# PowerNode2.net
KiCad netlist of a schematic drawn in EAGLE
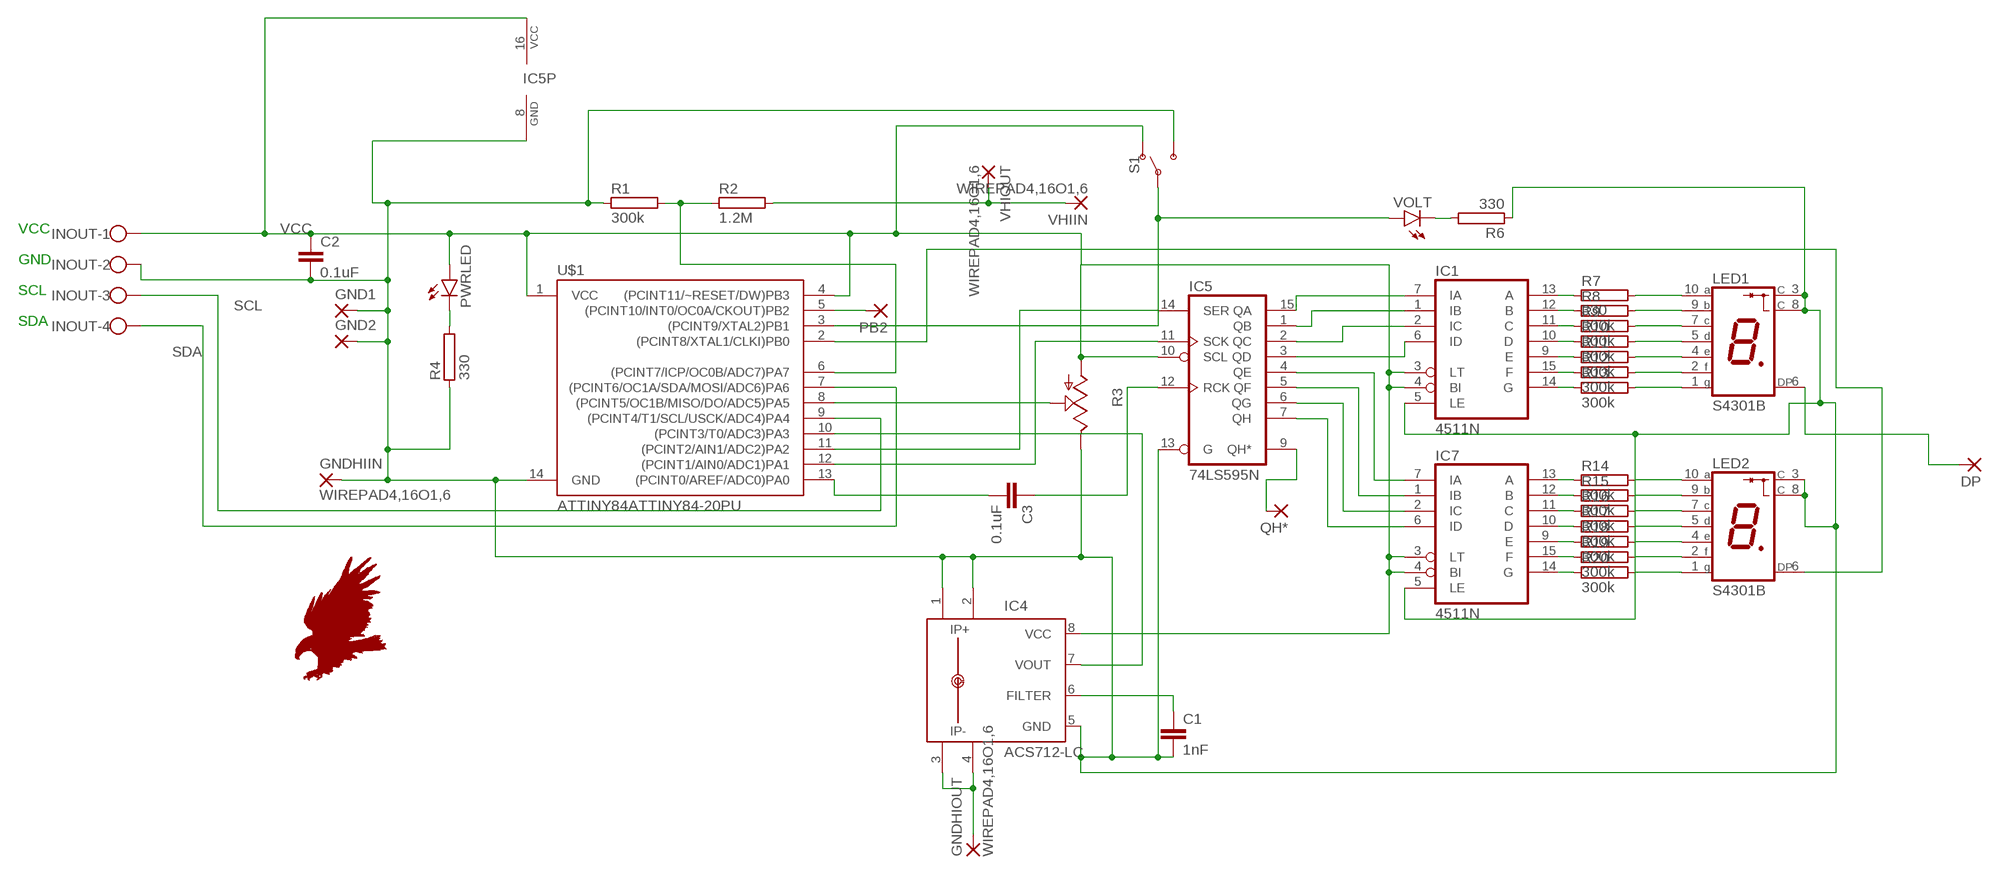
[diagram p0: schematic, sheet 1]

(export (version "E")
  (design (tool "Eeschema 10.0.6"))
  (components
    (comp (ref "C1")
      (value "1nF")
      (footprint "eagle-import:C5B3")
      (libsource (lib "eagle-import") (part "C5/3"))
    )
    (comp (ref "C2")
      (value "0.1uF")
      (footprint "eagle-import:C5B3")
      (libsource (lib "eagle-import") (part "C5/3"))
    )
    (comp (ref "C3")
      (value "0.1uF")
      (footprint "eagle-import:C5B3")
      (libsource (lib "eagle-import") (part "C5/3"))
    )
    (comp (ref "DP")
      (value "2,54/0,9")
      (footprint "eagle-import:2,54_0,9")
      (libsource (lib "eagle-import") (part "2,54/0,9"))
    )
    (comp (ref "GND1")
      (value "2,15/1,0")
      (footprint "eagle-import:2,15_1,0")
      (libsource (lib "eagle-import") (part "2,15/1,0"))
    )
    (comp (ref "GND2")
      (value "2,15/1,0")
      (footprint "eagle-import:2,15_1,0")
      (libsource (lib "eagle-import") (part "2,15/1,0"))
    )
    (comp (ref "GNDHIIN")
      (value "WIREPAD4,16O1,6")
      (footprint "eagle-import:4,16O1,6")
      (libsource (lib "eagle-import") (part "WIREPAD4,16O1,6"))
    )
    (comp (ref "GNDHIOUT")
      (value "WIREPAD4,16O1,6")
      (footprint "eagle-import:4,16O1,6")
      (libsource (lib "eagle-import") (part "WIREPAD4,16O1,6"))
    )
    (comp (ref "IC1")
      (value "4511N")
      (footprint "eagle-import:DIL16")
      (libsource (lib "eagle-import") (part "4511N"))
    )
    (comp (ref "IC4")
      (value "ACS712-LC")
      (footprint "eagle-import:SOIC8")
      (libsource (lib "eagle-import") (part "ACS712-LC"))
    )
    (comp (ref "IC5")
      (value "74LS595N")
      (footprint "eagle-import:DIL16")
      (libsource (lib "eagle-import") (part "74595NLS"))
    )
    (comp (ref "IC7")
      (value "4511N")
      (footprint "eagle-import:DIL16")
      (libsource (lib "eagle-import") (part "4511N"))
    )
    (comp (ref "INOUT")
      (value "W237-4")
      (footprint "eagle-import:W237-4")
      (libsource (lib "eagle-import") (part "W237-4"))
    )
    (comp (ref "LED1")
      (value "S4301B")
      (footprint "eagle-import:S4301B")
      (libsource (lib "eagle-import") (part "S4301B"))
    )
    (comp (ref "LED2")
      (value "S4301B")
      (footprint "eagle-import:S4301B")
      (libsource (lib "eagle-import") (part "S4301B"))
    )
    (comp (ref "PB2")
      (value "2,54/0,9")
      (footprint "eagle-import:2,54_0,9")
      (libsource (lib "eagle-import") (part "2,54/0,9"))
    )
    (comp (ref "PWRLED")
      (value "LED5MM")
      (footprint "eagle-import:LED5MM")
      (libsource (lib "eagle-import") (part "LED5MM"))
    )
    (comp (ref "QH*")
      (value "2,54/0,9")
      (footprint "eagle-import:2,54_0,9")
      (libsource (lib "eagle-import") (part "2,54/0,9"))
    )
    (comp (ref "R1")
      (value "300k")
      (footprint "eagle-import:KH206-8R")
      (libsource (lib "eagle-import") (part "RKH206-8R"))
    )
    (comp (ref "R2")
      (value "1.2M")
      (footprint "eagle-import:KH206-8R")
      (libsource (lib "eagle-import") (part "RKH206-8R"))
    )
    (comp (ref "R3")
      (value "TRIM_US-B25P")
      (footprint "eagle-import:B25P")
      (libsource (lib "eagle-import") (part "TRIM_US-B25P"))
    )
    (comp (ref "R4")
      (value "330")
      (footprint "eagle-import:KH206-8R")
      (libsource (lib "eagle-import") (part "RKH206-8R"))
    )
    (comp (ref "R6")
      (value "330")
      (footprint "eagle-import:KH206-8R")
      (libsource (lib "eagle-import") (part "RKH206-8R"))
    )
    (comp (ref "R7")
      (value "330")
      (footprint "eagle-import:KH206-8R")
      (libsource (lib "eagle-import") (part "RKH206-8R"))
    )
    (comp (ref "R8")
      (value "300k")
      (footprint "eagle-import:KH206-8R")
      (libsource (lib "eagle-import") (part "RKH206-8R"))
    )
    (comp (ref "R9")
      (value "300k")
      (footprint "eagle-import:KH206-8R")
      (libsource (lib "eagle-import") (part "RKH206-8R"))
    )
    (comp (ref "R10")
      (value "300k")
      (footprint "eagle-import:KH206-8R")
      (libsource (lib "eagle-import") (part "RKH206-8R"))
    )
    (comp (ref "R11")
      (value "300k")
      (footprint "eagle-import:KH206-8R")
      (libsource (lib "eagle-import") (part "RKH206-8R"))
    )
    (comp (ref "R12")
      (value "300k")
      (footprint "eagle-import:KH206-8R")
      (libsource (lib "eagle-import") (part "RKH206-8R"))
    )
    (comp (ref "R13")
      (value "300k")
      (footprint "eagle-import:KH206-8R")
      (libsource (lib "eagle-import") (part "RKH206-8R"))
    )
    (comp (ref "R14")
      (value "300k")
      (footprint "eagle-import:KH206-8R")
      (libsource (lib "eagle-import") (part "RKH206-8R"))
    )
    (comp (ref "R15")
      (value "300k")
      (footprint "eagle-import:KH206-8R")
      (libsource (lib "eagle-import") (part "RKH206-8R"))
    )
    (comp (ref "R16")
      (value "300k")
      (footprint "eagle-import:KH206-8R")
      (libsource (lib "eagle-import") (part "RKH206-8R"))
    )
    (comp (ref "R17")
      (value "300k")
      (footprint "eagle-import:KH206-8R")
      (libsource (lib "eagle-import") (part "RKH206-8R"))
    )
    (comp (ref "R18")
      (value "300k")
      (footprint "eagle-import:KH206-8R")
      (libsource (lib "eagle-import") (part "RKH206-8R"))
    )
    (comp (ref "R19")
      (value "300k")
      (footprint "eagle-import:KH206-8R")
      (libsource (lib "eagle-import") (part "RKH206-8R"))
    )
    (comp (ref "R20")
      (value "300k")
      (footprint "eagle-import:KH206-8R")
      (libsource (lib "eagle-import") (part "RKH206-8R"))
    )
    (comp (ref "S1")
      (value "SWITCH-SPDT-PTH-11.6X4.0MM")
      (footprint "eagle-import:SWITCH_SPDT_PTH_11.6X4.0MM")
      (libsource (lib "eagle-import") (part "SWITCH-SPDT-PTH-11.6X4.0MM"))
    )
    (comp (ref "U$1")
      (value "ATTINY84ATTINY84-20PU")
      (footprint "eagle-import:DIP14")
      (libsource (lib "eagle-import") (part "ATTINY84ATTINY84-20PU"))
    )
    (comp (ref "VHIIN")
      (value "WIREPAD4,16O1,6")
      (footprint "eagle-import:4,16O1,6")
      (libsource (lib "eagle-import") (part "WIREPAD4,16O1,6"))
    )
    (comp (ref "VHIOUT")
      (value "WIREPAD4,16O1,6")
      (footprint "eagle-import:4,16O1,6")
      (libsource (lib "eagle-import") (part "WIREPAD4,16O1,6"))
    )
    (comp (ref "VOLT")
      (value "LED5MM")
      (footprint "eagle-import:LED5MM")
      (libsource (lib "eagle-import") (part "LED5MM"))
    )
  )
  (nets
    (net (code "1") (name "/SCL") (class "Default")
      (node (ref "INOUT") (pin "3") (pinfunction "KL_3") (pintype "passive"))
      (node (ref "U$1") (pin "9") (pinfunction "(PCINT4/T1/SCL/USCK/ADC4)PA4_9") (pintype "bidirectional"))
    )
    (net (code "2") (name "/SDA") (class "Default")
      (node (ref "INOUT") (pin "4") (pinfunction "KL_4") (pintype "passive"))
      (node (ref "U$1") (pin "7") (pinfunction "(PCINT6/OC1A/SDA/MOSI/ADC6)PA6_7") (pintype "bidirectional"))
    )
    (net (code "3") (name "/VCC") (class "Default")
      (node (ref "C2") (pin "1") (pinfunction "1_1") (pintype "passive"))
      (node (ref "IC1") (pin "3") (pinfunction "LT_3") (pintype "input"))
      (node (ref "IC1") (pin "4") (pinfunction "BI_4") (pintype "input"))
      (node (ref "IC4") (pin "8") (pinfunction "VCC_8") (pintype "power_in"))
      (node (ref "IC5") (pin "10") (pinfunction "SCL_10") (pintype "input"))
      (node (ref "IC5") (pin "16") (pinfunction "VCC_16") (pintype "power_in"))
      (node (ref "IC7") (pin "3") (pinfunction "LT_3") (pintype "input"))
      (node (ref "IC7") (pin "4") (pinfunction "BI_4") (pintype "input"))
      (node (ref "INOUT") (pin "1") (pinfunction "KL_1") (pintype "passive"))
      (node (ref "PWRLED") (pin "A") (pinfunction "A_A") (pintype "passive"))
      (node (ref "R3") (pin "A") (pinfunction "A_A") (pintype "passive"))
      (node (ref "S1") (pin "1") (pinfunction "O_1") (pintype "passive"))
      (node (ref "U$1") (pin "1") (pinfunction "VCC_1") (pintype "bidirectional"))
      (node (ref "U$1") (pin "4") (pinfunction "(PCINT11/~{RESET/DW})PB3_4") (pintype "bidirectional"))
    )
    (net (code "4") (name "Net-(DP-P)") (class "Default")
      (node (ref "DP") (pin "1") (pinfunction "P_1") (pintype "passive"))
      (node (ref "LED1") (pin "6") (pinfunction "DP_6") (pintype "passive"))
    )
    (net (code "5") (name "Net-(GND1-P)") (class "Default")
      (node (ref "C1") (pin "2") (pinfunction "2_2") (pintype "passive"))
      (node (ref "C2") (pin "2") (pinfunction "2_2") (pintype "passive"))
      (node (ref "GND1") (pin "1") (pinfunction "P_1") (pintype "passive"))
      (node (ref "GND2") (pin "1") (pinfunction "P_1") (pintype "passive"))
      (node (ref "GNDHIIN") (pin "1") (pinfunction "P_1") (pintype "passive"))
      (node (ref "IC1") (pin "5") (pinfunction "LE_5") (pintype "input"))
      (node (ref "IC4") (pin "1") (pinfunction "IP+_1") (pintype "passive"))
      (node (ref "IC4") (pin "2") (pinfunction "IP+1_2") (pintype "passive"))
      (node (ref "IC4") (pin "5") (pinfunction "GND_5") (pintype "power_in"))
      (node (ref "IC5") (pin "13") (pinfunction "G_13") (pintype "input"))
      (node (ref "IC5") (pin "8") (pinfunction "GND_8") (pintype "power_in"))
      (node (ref "IC7") (pin "5") (pinfunction "LE_5") (pintype "input"))
      (node (ref "INOUT") (pin "2") (pinfunction "KL_2") (pintype "passive"))
      (node (ref "LED1") (pin "3") (pinfunction "C_3") (pintype "passive"))
      (node (ref "LED1") (pin "8") (pinfunction "C_8") (pintype "passive"))
      (node (ref "LED2") (pin "3") (pinfunction "C_3") (pintype "passive"))
      (node (ref "LED2") (pin "8") (pinfunction "C_8") (pintype "passive"))
      (node (ref "R1") (pin "1") (pinfunction "1_1") (pintype "passive"))
      (node (ref "R3") (pin "E") (pinfunction "E_E") (pintype "passive"))
      (node (ref "R4") (pin "1") (pinfunction "1_1") (pintype "passive"))
      (node (ref "R6") (pin "1") (pinfunction "1_1") (pintype "passive"))
      (node (ref "S1") (pin "3") (pinfunction "S_3") (pintype "passive"))
      (node (ref "U$1") (pin "14") (pinfunction "GND_14") (pintype "bidirectional"))
    )
    (net (code "6") (name "Net-(GNDHIOUT-P)") (class "Default")
      (node (ref "GNDHIOUT") (pin "1") (pinfunction "P_1") (pintype "passive"))
      (node (ref "IC4") (pin "3") (pinfunction "IP-_3") (pintype "passive"))
      (node (ref "IC4") (pin "4") (pinfunction "IP-1_4") (pintype "passive"))
    )
    (net (code "7") (name "Net-(IC1A-A)") (class "Default")
      (node (ref "IC1") (pin "13") (pinfunction "A_13") (pintype "output"))
      (node (ref "R7") (pin "1") (pinfunction "1_1") (pintype "passive"))
    )
    (net (code "8") (name "Net-(IC1A-B)") (class "Default")
      (node (ref "IC1") (pin "12") (pinfunction "B_12") (pintype "output"))
      (node (ref "R8") (pin "1") (pinfunction "1_1") (pintype "passive"))
    )
    (net (code "9") (name "Net-(IC1A-C)") (class "Default")
      (node (ref "IC1") (pin "11") (pinfunction "C_11") (pintype "output"))
      (node (ref "R9") (pin "1") (pinfunction "1_1") (pintype "passive"))
    )
    (net (code "10") (name "Net-(IC1A-D)") (class "Default")
      (node (ref "IC1") (pin "10") (pinfunction "D_10") (pintype "output"))
      (node (ref "R10") (pin "1") (pinfunction "1_1") (pintype "passive"))
    )
    (net (code "11") (name "Net-(IC1A-E)") (class "Default")
      (node (ref "IC1") (pin "9") (pinfunction "E_9") (pintype "output"))
      (node (ref "R11") (pin "1") (pinfunction "1_1") (pintype "passive"))
    )
    (net (code "12") (name "Net-(IC1A-F)") (class "Default")
      (node (ref "IC1") (pin "15") (pinfunction "F_15") (pintype "output"))
      (node (ref "R12") (pin "1") (pinfunction "1_1") (pintype "passive"))
    )
    (net (code "13") (name "Net-(IC1A-G)") (class "Default")
      (node (ref "IC1") (pin "14") (pinfunction "G_14") (pintype "output"))
      (node (ref "R13") (pin "1") (pinfunction "1_1") (pintype "passive"))
    )
    (net (code "14") (name "Net-(IC1A-IA)") (class "Default")
      (node (ref "IC1") (pin "7") (pinfunction "IA_7") (pintype "input"))
      (node (ref "IC5") (pin "15") (pinfunction "QA_15") (pintype "tri_state"))
    )
    (net (code "15") (name "Net-(IC1A-IB)") (class "Default")
      (node (ref "IC1") (pin "1") (pinfunction "IB_1") (pintype "input"))
      (node (ref "IC5") (pin "1") (pinfunction "QB_1") (pintype "tri_state"))
    )
    (net (code "16") (name "Net-(IC1A-IC)") (class "Default")
      (node (ref "IC1") (pin "2") (pinfunction "IC_2") (pintype "input"))
      (node (ref "IC5") (pin "2") (pinfunction "QC_2") (pintype "tri_state"))
    )
    (net (code "17") (name "Net-(IC1A-ID)") (class "Default")
      (node (ref "IC1") (pin "6") (pinfunction "ID_6") (pintype "input"))
      (node (ref "IC5") (pin "3") (pinfunction "QD_3") (pintype "tri_state"))
    )
    (net (code "18") (name "Net-(IC4-FILTER)") (class "Default")
      (node (ref "C1") (pin "1") (pinfunction "1_1") (pintype "passive"))
      (node (ref "IC4") (pin "6") (pinfunction "FILTER_6") (pintype "bidirectional"))
    )
    (net (code "19") (name "Net-(IC4-VOUT)") (class "Default")
      (node (ref "IC4") (pin "7") (pinfunction "VOUT_7") (pintype "output"))
      (node (ref "U$1") (pin "10") (pinfunction "(PCINT3/T0/ADC3)PA3_10") (pintype "bidirectional"))
    )
    (net (code "20") (name "Net-(IC5A-QE)") (class "Default")
      (node (ref "IC5") (pin "4") (pinfunction "QE_4") (pintype "tri_state"))
      (node (ref "IC7") (pin "7") (pinfunction "IA_7") (pintype "input"))
    )
    (net (code "21") (name "Net-(IC5A-QF)") (class "Default")
      (node (ref "IC5") (pin "5") (pinfunction "QF_5") (pintype "tri_state"))
      (node (ref "IC7") (pin "1") (pinfunction "IB_1") (pintype "input"))
    )
    (net (code "22") (name "Net-(IC5A-QG)") (class "Default")
      (node (ref "IC5") (pin "6") (pinfunction "QG_6") (pintype "tri_state"))
      (node (ref "IC7") (pin "2") (pinfunction "IC_2") (pintype "input"))
    )
    (net (code "23") (name "Net-(IC5A-QH)") (class "Default")
      (node (ref "IC5") (pin "7") (pinfunction "QH_7") (pintype "tri_state"))
      (node (ref "IC7") (pin "6") (pinfunction "ID_6") (pintype "input"))
    )
    (net (code "24") (name "Net-(IC5A-QH*)") (class "Default")
      (node (ref "IC5") (pin "9") (pinfunction "QH*_9") (pintype "tri_state"))
      (node (ref "QH*") (pin "1") (pinfunction "P_1") (pintype "passive"))
    )
    (net (code "25") (name "Net-(IC5A-RCK)") (class "Default")
      (node (ref "C3") (pin "1") (pinfunction "1_1") (pintype "passive"))
      (node (ref "IC5") (pin "12") (pinfunction "RCK_12") (pintype "input"))
    )
    (net (code "26") (name "Net-(IC5A-SCK)") (class "Default")
      (node (ref "IC5") (pin "11") (pinfunction "SCK_11") (pintype "input"))
      (node (ref "U$1") (pin "12") (pinfunction "(PCINT1/AIN0/ADC1)PA1_12") (pintype "bidirectional"))
    )
    (net (code "27") (name "Net-(IC5A-SER)") (class "Default")
      (node (ref "IC5") (pin "14") (pinfunction "SER_14") (pintype "input"))
      (node (ref "U$1") (pin "11") (pinfunction "(PCINT2/AIN1/ADC2)PA2_11") (pintype "bidirectional"))
    )
    (net (code "28") (name "Net-(IC7A-A)") (class "Default")
      (node (ref "IC7") (pin "13") (pinfunction "A_13") (pintype "output"))
      (node (ref "R14") (pin "1") (pinfunction "1_1") (pintype "passive"))
    )
    (net (code "29") (name "Net-(IC7A-B)") (class "Default")
      (node (ref "IC7") (pin "12") (pinfunction "B_12") (pintype "output"))
      (node (ref "R15") (pin "1") (pinfunction "1_1") (pintype "passive"))
    )
    (net (code "30") (name "Net-(IC7A-C)") (class "Default")
      (node (ref "IC7") (pin "11") (pinfunction "C_11") (pintype "output"))
      (node (ref "R16") (pin "1") (pinfunction "1_1") (pintype "passive"))
    )
    (net (code "31") (name "Net-(IC7A-D)") (class "Default")
      (node (ref "IC7") (pin "10") (pinfunction "D_10") (pintype "output"))
      (node (ref "R17") (pin "1") (pinfunction "1_1") (pintype "passive"))
    )
    (net (code "32") (name "Net-(IC7A-E)") (class "Default")
      (node (ref "IC7") (pin "9") (pinfunction "E_9") (pintype "output"))
      (node (ref "R18") (pin "1") (pinfunction "1_1") (pintype "passive"))
    )
    (net (code "33") (name "Net-(IC7A-F)") (class "Default")
      (node (ref "IC7") (pin "15") (pinfunction "F_15") (pintype "output"))
      (node (ref "R19") (pin "1") (pinfunction "1_1") (pintype "passive"))
    )
    (net (code "34") (name "Net-(IC7A-G)") (class "Default")
      (node (ref "IC7") (pin "14") (pinfunction "G_14") (pintype "output"))
      (node (ref "R20") (pin "1") (pinfunction "1_1") (pintype "passive"))
    )
    (net (code "35") (name "Net-(LED1-A)") (class "Default")
      (node (ref "LED1") (pin "10") (pinfunction "A_10") (pintype "passive"))
      (node (ref "R7") (pin "2") (pinfunction "2_2") (pintype "passive"))
    )
    (net (code "36") (name "Net-(LED1-B)") (class "Default")
      (node (ref "LED1") (pin "9") (pinfunction "B_9") (pintype "passive"))
      (node (ref "R8") (pin "2") (pinfunction "2_2") (pintype "passive"))
    )
    (net (code "37") (name "Net-(LED1-C-Pad7)") (class "Default")
      (node (ref "LED1") (pin "7") (pinfunction "C_7") (pintype "passive"))
      (node (ref "R9") (pin "2") (pinfunction "2_2") (pintype "passive"))
    )
    (net (code "38") (name "Net-(LED1-D)") (class "Default")
      (node (ref "LED1") (pin "5") (pinfunction "D_5") (pintype "passive"))
      (node (ref "R10") (pin "2") (pinfunction "2_2") (pintype "passive"))
    )
    (net (code "39") (name "Net-(LED1-E)") (class "Default")
      (node (ref "LED1") (pin "4") (pinfunction "E_4") (pintype "passive"))
      (node (ref "R11") (pin "2") (pinfunction "2_2") (pintype "passive"))
    )
    (net (code "40") (name "Net-(LED1-F)") (class "Default")
      (node (ref "LED1") (pin "2") (pinfunction "F_2") (pintype "passive"))
      (node (ref "R12") (pin "2") (pinfunction "2_2") (pintype "passive"))
    )
    (net (code "41") (name "Net-(LED1-G)") (class "Default")
      (node (ref "LED1") (pin "1") (pinfunction "G_1") (pintype "passive"))
      (node (ref "R13") (pin "2") (pinfunction "2_2") (pintype "passive"))
    )
    (net (code "42") (name "Net-(LED2-A)") (class "Default")
      (node (ref "LED2") (pin "10") (pinfunction "A_10") (pintype "passive"))
      (node (ref "R14") (pin "2") (pinfunction "2_2") (pintype "passive"))
    )
    (net (code "43") (name "Net-(LED2-B)") (class "Default")
      (node (ref "LED2") (pin "9") (pinfunction "B_9") (pintype "passive"))
      (node (ref "R15") (pin "2") (pinfunction "2_2") (pintype "passive"))
    )
    (net (code "44") (name "Net-(LED2-C-Pad7)") (class "Default")
      (node (ref "LED2") (pin "7") (pinfunction "C_7") (pintype "passive"))
      (node (ref "R16") (pin "2") (pinfunction "2_2") (pintype "passive"))
    )
    (net (code "45") (name "Net-(LED2-D)") (class "Default")
      (node (ref "LED2") (pin "5") (pinfunction "D_5") (pintype "passive"))
      (node (ref "R17") (pin "2") (pinfunction "2_2") (pintype "passive"))
    )
    (net (code "46") (name "Net-(LED2-DP)") (class "Default")
      (node (ref "LED2") (pin "6") (pinfunction "DP_6") (pintype "passive"))
      (node (ref "U$1") (pin "2") (pinfunction "(PCINT8/XTAL1/CLKI)PB0_2") (pintype "bidirectional"))
    )
    (net (code "47") (name "Net-(LED2-E)") (class "Default")
      (node (ref "LED2") (pin "4") (pinfunction "E_4") (pintype "passive"))
      (node (ref "R18") (pin "2") (pinfunction "2_2") (pintype "passive"))
    )
    (net (code "48") (name "Net-(LED2-F)") (class "Default")
      (node (ref "LED2") (pin "2") (pinfunction "F_2") (pintype "passive"))
      (node (ref "R19") (pin "2") (pinfunction "2_2") (pintype "passive"))
    )
    (net (code "49") (name "Net-(LED2-G)") (class "Default")
      (node (ref "LED2") (pin "1") (pinfunction "G_1") (pintype "passive"))
      (node (ref "R20") (pin "2") (pinfunction "2_2") (pintype "passive"))
    )
    (net (code "50") (name "Net-(PB2-P)") (class "Default")
      (node (ref "PB2") (pin "1") (pinfunction "P_1") (pintype "passive"))
      (node (ref "U$1") (pin "5") (pinfunction "(PCINT10/INT0/OC0A/CKOUT)PB2_5") (pintype "bidirectional"))
    )
    (net (code "51") (name "Net-(PWRLED-C)") (class "Default")
      (node (ref "PWRLED") (pin "K") (pinfunction "C_K") (pintype "passive"))
      (node (ref "R4") (pin "2") (pinfunction "2_2") (pintype "passive"))
    )
    (net (code "52") (name "Net-(S1-P)") (class "Default")
      (node (ref "S1") (pin "2") (pinfunction "P_2") (pintype "passive"))
      (node (ref "U$1") (pin "3") (pinfunction "(PCINT9/XTAL2)PB1_3") (pintype "bidirectional"))
      (node (ref "VOLT") (pin "A") (pinfunction "A_A") (pintype "passive"))
    )
    (net (code "53") (name "Net-(U$1-(PCINT0{slash}AREF{slash}ADC0)PA0)") (class "Default")
      (node (ref "C3") (pin "2") (pinfunction "2_2") (pintype "passive"))
      (node (ref "U$1") (pin "13") (pinfunction "(PCINT0/AREF/ADC0)PA0_13") (pintype "bidirectional"))
    )
    (net (code "54") (name "Net-(U$1-(PCINT5{slash}OC1B{slash}MISO{slash}DO{slash}ADC5)PA5)") (class "Default")
      (node (ref "R3") (pin "S") (pinfunction "S_S") (pintype "passive"))
      (node (ref "U$1") (pin "8") (pinfunction "(PCINT5/OC1B/MISO/DO/ADC5)PA5_8") (pintype "bidirectional"))
    )
    (net (code "55") (name "Net-(U$1-(PCINT7{slash}ICP{slash}OC0B{slash}ADC7)PA7)") (class "Default")
      (node (ref "R1") (pin "2") (pinfunction "2_2") (pintype "passive"))
      (node (ref "R2") (pin "1") (pinfunction "1_1") (pintype "passive"))
      (node (ref "U$1") (pin "6") (pinfunction "(PCINT7/ICP/OC0B/ADC7)PA7_6") (pintype "bidirectional"))
    )
    (net (code "56") (name "Net-(VHIIN-P)") (class "Default")
      (node (ref "R2") (pin "2") (pinfunction "2_2") (pintype "passive"))
      (node (ref "VHIIN") (pin "1") (pinfunction "P_1") (pintype "passive"))
      (node (ref "VHIOUT") (pin "1") (pinfunction "P_1") (pintype "passive"))
    )
    (net (code "57") (name "Net-(VOLT-C)") (class "Default")
      (node (ref "R6") (pin "2") (pinfunction "2_2") (pintype "passive"))
      (node (ref "VOLT") (pin "K") (pinfunction "C_K") (pintype "passive"))
    )
  )
)
